# LilyPad-Simblee.net
KiCad netlist of a schematic drawn in EAGLE
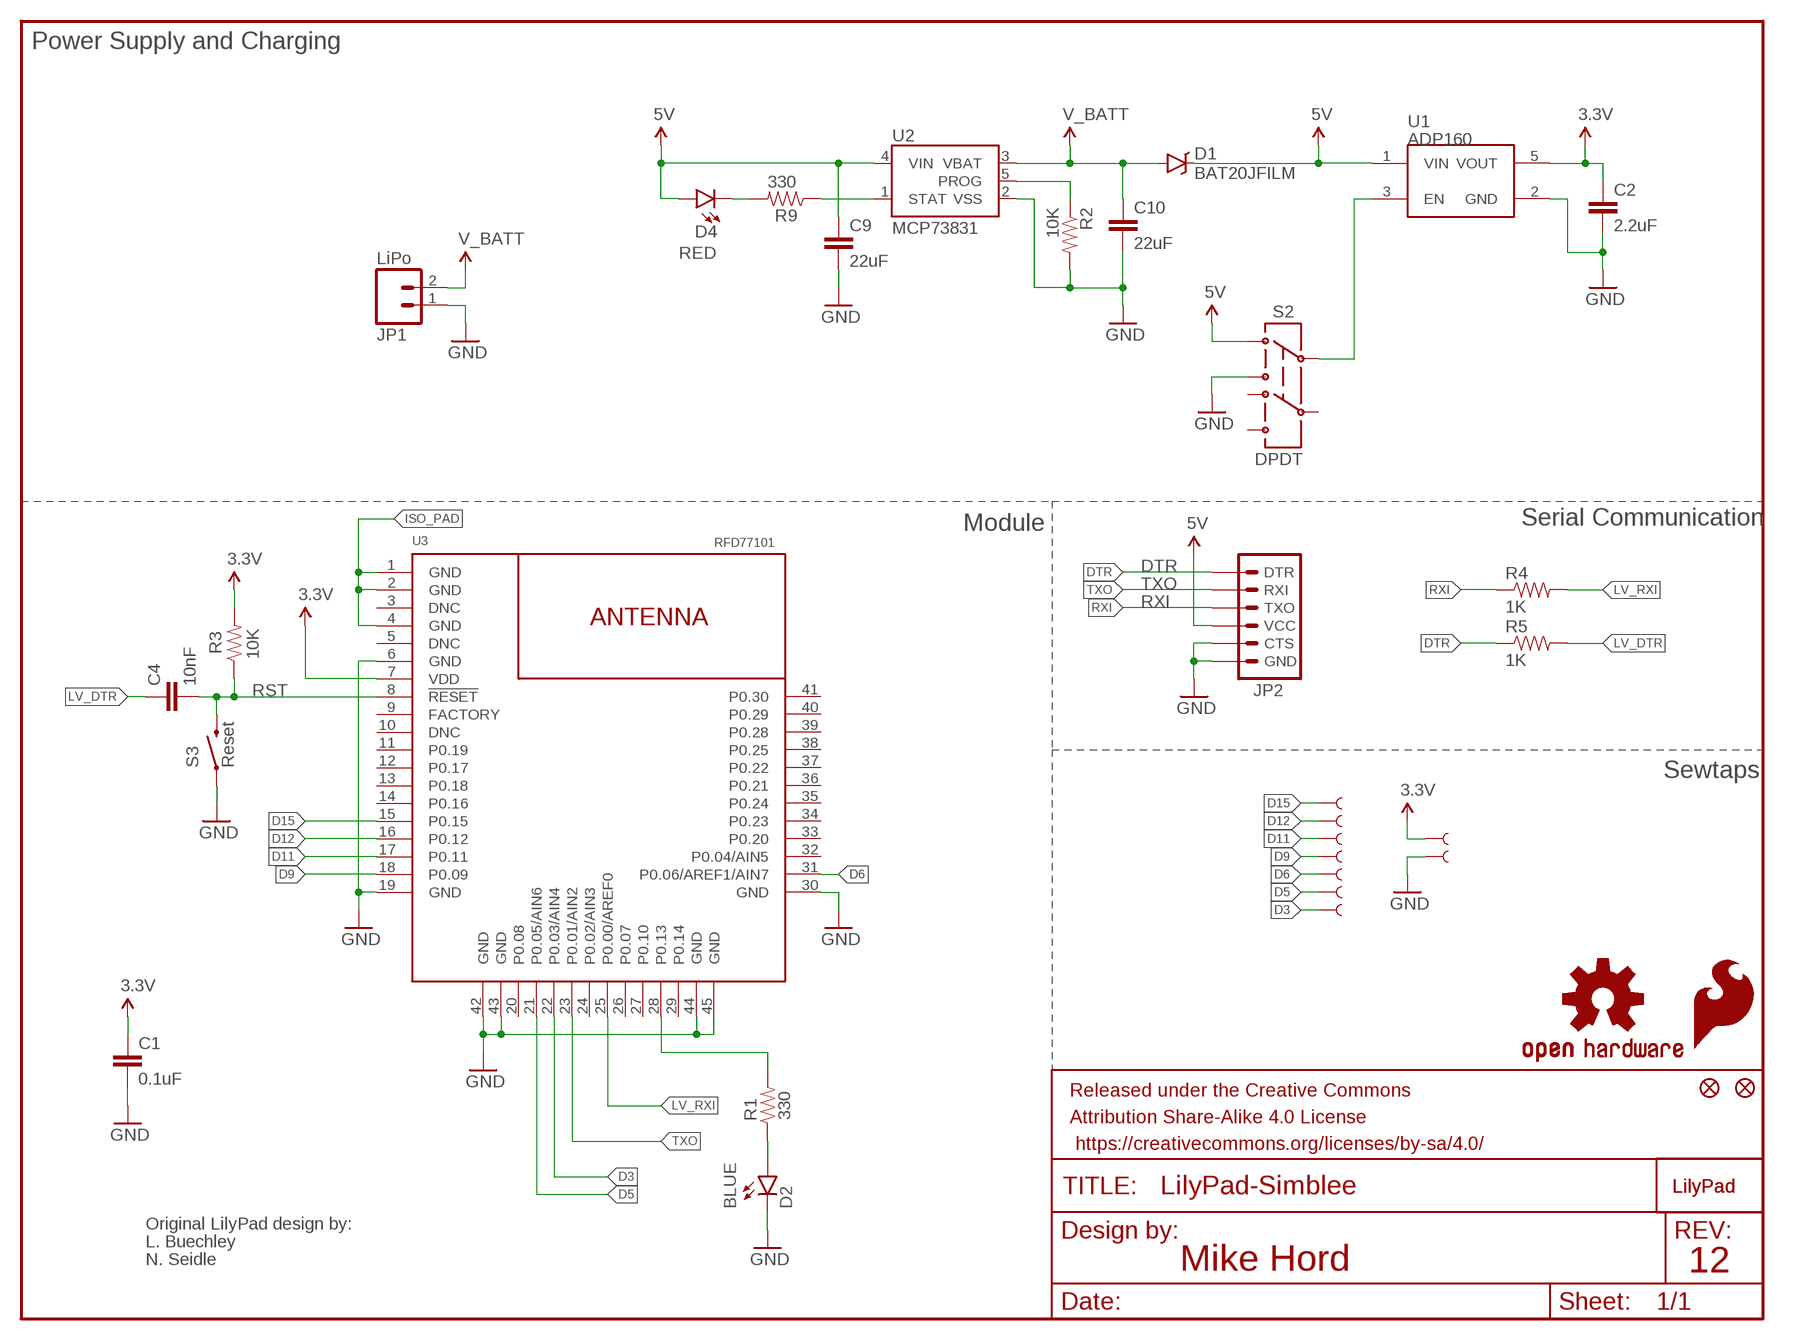
[diagram p0: schematic, sheet 1]

(export (version "E")
  (design (tool "Eeschema 10.0.6"))
  (components
    (comp (ref "A4/18")
      (value "SEWTAP9")
      (footprint "eagle-import:PETAL-LONG-1-2SIDE")
      (libsource (lib "eagle-import") (part "SEWTAP9"))
    )
    (comp (ref "A5/19")
      (value "SEWTAP9")
      (footprint "eagle-import:PETAL-LONG-1-2SIDE")
      (libsource (lib "eagle-import") (part "SEWTAP9"))
    )
    (comp (ref "C1")
      (value "0.1uF")
      (footprint "eagle-import:0603-CAP")
      (libsource (lib "eagle-import") (part "0.1UF-25V(+80/-20%)(0603)"))
    )
    (comp (ref "C2")
      (value "2.2uF")
      (footprint "eagle-import:0603-CAP")
      (libsource (lib "eagle-import") (part "2.2UF-10V-20%(0603)"))
    )
    (comp (ref "C4")
      (value "10nF")
      (footprint "eagle-import:0603-CAP")
      (libsource (lib "eagle-import") (part "10NF/10000PF-50V-10%(0603)"))
    )
    (comp (ref "C9")
      (value "22uF")
      (footprint "eagle-import:0805")
      (libsource (lib "eagle-import") (part "22UF-6.3V-20%(0805)"))
    )
    (comp (ref "C10")
      (value "22uF")
      (footprint "eagle-import:0805")
      (libsource (lib "eagle-import") (part "22UF-6.3V-20%(0805)"))
    )
    (comp (ref "D1")
      (value "BAT20JFILM")
      (footprint "eagle-import:SOD-323")
      (libsource (lib "eagle-import") (part "BAT20JFILM"))
    )
    (comp (ref "D2")
      (value "BLUE")
      (footprint "eagle-import:LED-0603")
      (libsource (lib "eagle-import") (part "LED-BLUE0603"))
    )
    (comp (ref "D4")
      (value "RED")
      (footprint "eagle-import:LED-0603")
      (libsource (lib "eagle-import") (part "LED-RED0603"))
    )
    (comp (ref "FID1")
      (value "FIDUCIALUFIDUCIAL")
      (footprint "eagle-import:MICRO-FIDUCIAL")
      (libsource (lib "eagle-import") (part "FIDUCIALUFIDUCIAL"))
    )
    (comp (ref "FID2")
      (value "FIDUCIALUFIDUCIAL")
      (footprint "eagle-import:MICRO-FIDUCIAL")
      (libsource (lib "eagle-import") (part "FIDUCIALUFIDUCIAL"))
    )
    (comp (ref "FRAME1")
      (value "FRAME-LETTER")
      (footprint "eagle-import:CREATIVE_COMMONS")
      (libsource (lib "eagle-import") (part "FRAME-LETTER"))
    )
    (comp (ref "JP1")
      (value "LiPo")
      (footprint "eagle-import:JST-2-SMD")
      (libsource (lib "eagle-import") (part "M02-JST-2MM-SMT"))
    )
    (comp (ref "JP2")
      (value "ARDUINO_SERIAL_PROGRAMSMD")
      (footprint "eagle-import:1X06-SMD")
      (fields (field (name "PROD_ID") "CONN-08971"))
      (libsource (lib "eagle-import") (part "ARDUINO_SERIAL_PROGRAMSMD"))
    )
    (comp (ref "LOGO1")
      (value "SFE_LOGO_FLAME.1COP")
      (footprint "eagle-import:SFE_LOGO_FLAME_COPPER_.1")
      (libsource (lib "eagle-import") (part "SFE_LOGO_FLAME.1COP"))
    )
    (comp (ref "LOGO2")
      (value "OSHW-LOGOS-COPPER")
      (footprint "eagle-import:OSHW-LOGO-S_COPPER")
      (libsource (lib "eagle-import") (part "OSHW-LOGOS-COPPER"))
    )
    (comp (ref "R1")
      (value "330")
      (footprint "eagle-import:0603-RES")
      (libsource (lib "eagle-import") (part "330OHM1/10W1%(0603)"))
    )
    (comp (ref "R2")
      (value "10K")
      (footprint "eagle-import:0603-RES")
      (libsource (lib "eagle-import") (part "10KOHM-1/10W-1%(0603)0603"))
    )
    (comp (ref "R3")
      (value "10K")
      (footprint "eagle-import:0603-RES")
      (libsource (lib "eagle-import") (part "10KOHM-1/10W-1%(0603)0603"))
    )
    (comp (ref "R4")
      (value "1K")
      (footprint "eagle-import:0603-RES")
      (libsource (lib "eagle-import") (part "1KOHM-1/10W-1%(0603)"))
    )
    (comp (ref "R5")
      (value "1K")
      (footprint "eagle-import:0603-RES")
      (libsource (lib "eagle-import") (part "1KOHM-1/10W-1%(0603)"))
    )
    (comp (ref "R9")
      (value "330")
      (footprint "eagle-import:0603-RES")
      (libsource (lib "eagle-import") (part "330OHM1/10W1%(0603)"))
    )
    (comp (ref "S2")
      (value "DPDT")
      (footprint "eagle-import:AYZ0202")
      (libsource (lib "eagle-import") (part "SWITCH-DPDTAYZ0202"))
    )
    (comp (ref "S3")
      (value "Reset")
      (footprint "eagle-import:TACTILE-SWITCH-SMD")
      (libsource (lib "eagle-import") (part "SWITCH-MOMENTARY-2SMD"))
    )
    (comp (ref "U$1")
      (value "LOGO-LPL")
      (footprint "eagle-import:LOGO-L")
      (libsource (lib "eagle-import") (part "LOGO-LPL"))
    )
    (comp (ref "U$2")
      (value "LOGO-LPLP")
      (footprint "eagle-import:LOGO-LILYPAD")
      (libsource (lib "eagle-import") (part "LOGO-LPLP"))
    )
    (comp (ref "U$4")
      (value "SEWTAP9")
      (footprint "eagle-import:PETAL-LONG-1-2SIDE")
      (libsource (lib "eagle-import") (part "SEWTAP9"))
    )
    (comp (ref "U$35")
      (value "SEWTAP9")
      (footprint "eagle-import:PETAL-LONG-1-2SIDE")
      (libsource (lib "eagle-import") (part "SEWTAP9"))
    )
    (comp (ref "U$37")
      (value "SEWTAP9")
      (footprint "eagle-import:PETAL-LONG-1-2SIDE")
      (libsource (lib "eagle-import") (part "SEWTAP9"))
    )
    (comp (ref "U$39")
      (value "SEWTAP9")
      (footprint "eagle-import:PETAL-LONG-1-2SIDE")
      (libsource (lib "eagle-import") (part "SEWTAP9"))
    )
    (comp (ref "U$41")
      (value "SEWTAP9")
      (footprint "eagle-import:PETAL-LONG-1-2SIDE")
      (libsource (lib "eagle-import") (part "SEWTAP9"))
    )
    (comp (ref "U$43")
      (value "SEWTAP9")
      (footprint "eagle-import:PETAL-LONG-1-2SIDE")
      (libsource (lib "eagle-import") (part "SEWTAP9"))
    )
    (comp (ref "U$45")
      (value "SEWTAP9")
      (footprint "eagle-import:PETAL-LONG-1-2SIDE")
      (libsource (lib "eagle-import") (part "SEWTAP9"))
    )
    (comp (ref "U1")
      (value "ADP160")
      (footprint "eagle-import:SOT23-5")
      (libsource (lib "eagle-import") (part "ADP160"))
    )
    (comp (ref "U2")
      (value "MCP73831")
      (footprint "eagle-import:SOT23-5")
      (libsource (lib "eagle-import") (part "MCP73831"))
    )
    (comp (ref "U3")
      (value "RFD77101")
      (footprint "eagle-import:RFD77101")
      (libsource (lib "eagle-import") (part "RFD77101"))
    )
  )
  (nets
    (net (code "1") (name "/RST") (class "Default")
      (node (ref "C4") (pin "2") (pinfunction "2_2") (pintype "passive"))
      (node (ref "R3") (pin "1") (pinfunction "1_1") (pintype "passive"))
      (node (ref "S3") (pin "3") (pinfunction "2_3") (pintype "passive"))
      (node (ref "U3") (pin "8") (pinfunction "~{RESET}_8") (pintype "input"))
    )
    (net (code "2") (name "3.3V") (class "Default")
      (node (ref "C1") (pin "1") (pinfunction "1_1") (pintype "passive"))
      (node (ref "C2") (pin "1") (pinfunction "1_1") (pintype "passive"))
      (node (ref "R3") (pin "2") (pinfunction "2_2") (pintype "passive"))
      (node (ref "U$43") (pin "1") (pinfunction "1_1") (pintype "bidirectional"))
      (node (ref "U1") (pin "5") (pinfunction "VOUT_5") (pintype "bidirectional"))
      (node (ref "U3") (pin "7") (pinfunction "VDD_7") (pintype "power_in"))
    )
    (net (code "3") (name "5V") (class "Default")
      (node (ref "C9") (pin "1") (pinfunction "1_1") (pintype "passive"))
      (node (ref "D1") (pin "C") (pinfunction "C_C") (pintype "passive"))
      (node (ref "D4") (pin "A") (pinfunction "A_A") (pintype "passive"))
      (node (ref "JP2") (pin "4") (pinfunction "VCC_4") (pintype "passive"))
      (node (ref "S2") (pin "1") (pinfunction "1_1") (pintype "bidirectional"))
      (node (ref "U1") (pin "1") (pinfunction "VIN_1") (pintype "bidirectional"))
      (node (ref "U2") (pin "4") (pinfunction "VIN_4") (pintype "power_in"))
    )
    (net (code "4") (name "D3") (class "Default")
      (node (ref "A5/19") (pin "1") (pinfunction "1_1") (pintype "bidirectional"))
      (node (ref "U3") (pin "22") (pinfunction "P0.03/AIN4_22") (pintype "bidirectional"))
    )
    (net (code "5") (name "D5") (class "Default")
      (node (ref "U$39") (pin "1") (pinfunction "1_1") (pintype "bidirectional"))
      (node (ref "U3") (pin "21") (pinfunction "P0.05/AIN6_21") (pintype "bidirectional"))
    )
    (net (code "6") (name "D6") (class "Default")
      (node (ref "A4/18") (pin "1") (pinfunction "1_1") (pintype "bidirectional"))
      (node (ref "U3") (pin "31") (pinfunction "P0.06/AREF1/AIN7_31") (pintype "bidirectional"))
    )
    (net (code "7") (name "D9") (class "Default")
      (node (ref "U$4") (pin "1") (pinfunction "1_1") (pintype "bidirectional"))
      (node (ref "U3") (pin "18") (pinfunction "P0.09_18") (pintype "bidirectional"))
    )
    (net (code "8") (name "D11") (class "Default")
      (node (ref "U$45") (pin "1") (pinfunction "1_1") (pintype "bidirectional"))
      (node (ref "U3") (pin "17") (pinfunction "P0.11_17") (pintype "bidirectional"))
    )
    (net (code "9") (name "D12") (class "Default")
      (node (ref "U$37") (pin "1") (pinfunction "1_1") (pintype "bidirectional"))
      (node (ref "U3") (pin "16") (pinfunction "P0.12_16") (pintype "bidirectional"))
    )
    (net (code "10") (name "D15") (class "Default")
      (node (ref "U$35") (pin "1") (pinfunction "1_1") (pintype "bidirectional"))
      (node (ref "U3") (pin "15") (pinfunction "P0.15_15") (pintype "bidirectional"))
    )
    (net (code "11") (name "DTR") (class "Default")
      (node (ref "JP2") (pin "1") (pinfunction "DTR_1") (pintype "passive"))
      (node (ref "R5") (pin "1") (pinfunction "1_1") (pintype "passive"))
    )
    (net (code "12") (name "GND") (class "Default")
      (node (ref "C1") (pin "2") (pinfunction "2_2") (pintype "passive"))
      (node (ref "C10") (pin "2") (pinfunction "2_2") (pintype "passive"))
      (node (ref "C2") (pin "2") (pinfunction "2_2") (pintype "passive"))
      (node (ref "C9") (pin "2") (pinfunction "2_2") (pintype "passive"))
      (node (ref "D2") (pin "C") (pinfunction "C_C") (pintype "passive"))
      (node (ref "JP1") (pin "1") (pinfunction "2_1") (pintype "passive"))
      (node (ref "JP2") (pin "5") (pinfunction "CTS_5") (pintype "passive"))
      (node (ref "JP2") (pin "6") (pinfunction "GND_6") (pintype "passive"))
      (node (ref "R2") (pin "2") (pinfunction "2_2") (pintype "passive"))
      (node (ref "S2") (pin "3") (pinfunction "3_3") (pintype "bidirectional"))
      (node (ref "S3") (pin "1") (pinfunction "1_1") (pintype "passive"))
      (node (ref "U$41") (pin "1") (pinfunction "1_1") (pintype "bidirectional"))
      (node (ref "U1") (pin "2") (pinfunction "GND_2") (pintype "bidirectional"))
      (node (ref "U2") (pin "2") (pinfunction "VSS_2") (pintype "power_in"))
      (node (ref "U3") (pin "19") (pinfunction "GND_19") (pintype "power_in"))
      (node (ref "U3") (pin "30") (pinfunction "GND_30") (pintype "power_in"))
      (node (ref "U3") (pin "42") (pinfunction "GND_42") (pintype "power_in"))
      (node (ref "U3") (pin "43") (pinfunction "GND_43") (pintype "power_in"))
      (node (ref "U3") (pin "44") (pinfunction "GND_44") (pintype "power_in"))
      (node (ref "U3") (pin "45") (pinfunction "GND_45") (pintype "power_in"))
      (node (ref "U3") (pin "6") (pinfunction "GND_6") (pintype "power_in"))
    )
    (net (code "13") (name "ISO_PAD") (class "Default")
      (node (ref "U3") (pin "1") (pinfunction "GND_1") (pintype "power_in"))
      (node (ref "U3") (pin "2") (pinfunction "GND_2") (pintype "power_in"))
      (node (ref "U3") (pin "4") (pinfunction "GND_4") (pintype "power_in"))
    )
    (net (code "14") (name "LV_DTR") (class "Default")
      (node (ref "C4") (pin "1") (pinfunction "1_1") (pintype "passive"))
      (node (ref "R5") (pin "2") (pinfunction "2_2") (pintype "passive"))
    )
    (net (code "15") (name "LV_RXI") (class "Default")
      (node (ref "R4") (pin "2") (pinfunction "2_2") (pintype "passive"))
      (node (ref "U3") (pin "25") (pinfunction "P0.00/AREF0_25") (pintype "bidirectional"))
    )
    (net (code "16") (name "Net-(D2-PadA)") (class "Default")
      (node (ref "D2") (pin "A") (pinfunction "A_A") (pintype "passive"))
      (node (ref "R1") (pin "1") (pinfunction "1_1") (pintype "passive"))
    )
    (net (code "17") (name "Net-(D4-PadC)") (class "Default")
      (node (ref "D4") (pin "C") (pinfunction "C_C") (pintype "passive"))
      (node (ref "R9") (pin "2") (pinfunction "2_2") (pintype "passive"))
    )
    (net (code "18") (name "Net-(U1-EN)") (class "Default")
      (node (ref "S2") (pin "2") (pinfunction "2_2") (pintype "bidirectional"))
      (node (ref "U1") (pin "3") (pinfunction "EN_3") (pintype "bidirectional"))
    )
    (net (code "19") (name "Net-(U2-PROG)") (class "Default")
      (node (ref "R2") (pin "1") (pinfunction "1_1") (pintype "passive"))
      (node (ref "U2") (pin "5") (pinfunction "PROG_5") (pintype "input"))
    )
    (net (code "20") (name "Net-(U2-STAT)") (class "Default")
      (node (ref "R9") (pin "1") (pinfunction "1_1") (pintype "passive"))
      (node (ref "U2") (pin "1") (pinfunction "STAT_1") (pintype "output"))
    )
    (net (code "21") (name "Net-(U3-P0.13)") (class "Default")
      (node (ref "R1") (pin "2") (pinfunction "2_2") (pintype "passive"))
      (node (ref "U3") (pin "28") (pinfunction "P0.13_28") (pintype "bidirectional"))
    )
    (net (code "22") (name "RXI") (class "Default")
      (node (ref "JP2") (pin "3") (pinfunction "TXO_3") (pintype "passive"))
      (node (ref "R4") (pin "1") (pinfunction "1_1") (pintype "passive"))
    )
    (net (code "23") (name "TXO") (class "Default")
      (node (ref "JP2") (pin "2") (pinfunction "RXI_2") (pintype "passive"))
      (node (ref "U3") (pin "23") (pinfunction "P0.01/AIN2_23") (pintype "bidirectional"))
    )
    (net (code "24") (name "V_BATT") (class "Default")
      (node (ref "C10") (pin "1") (pinfunction "1_1") (pintype "passive"))
      (node (ref "D1") (pin "A") (pinfunction "A_A") (pintype "passive"))
      (node (ref "JP1") (pin "2") (pinfunction "1_2") (pintype "passive"))
      (node (ref "U2") (pin "3") (pinfunction "VBAT_3") (pintype "power_in"))
    )
    (net (code "25") (name "unconnected-(S2-Pad4)") (class "Default")
      (node (ref "S2") (pin "4") (pinfunction "4_4") (pintype "bidirectional"))
    )
    (net (code "26") (name "unconnected-(S2-Pad5)") (class "Default")
      (node (ref "S2") (pin "5") (pinfunction "5_5") (pintype "bidirectional"))
    )
    (net (code "27") (name "unconnected-(S2-Pad6)") (class "Default")
      (node (ref "S2") (pin "6") (pinfunction "6_6") (pintype "bidirectional"))
    )
    (net (code "28") (name "unconnected-(U3-DNC-Pad3)") (class "Default")
      (node (ref "U3") (pin "3") (pinfunction "DNC_3") (pintype "no_connect"))
    )
    (net (code "29") (name "unconnected-(U3-DNC-Pad5)") (class "Default")
      (node (ref "U3") (pin "5") (pinfunction "DNC_5") (pintype "no_connect"))
    )
    (net (code "30") (name "unconnected-(U3-DNC-Pad10)") (class "Default")
      (node (ref "U3") (pin "10") (pinfunction "DNC_10") (pintype "no_connect"))
    )
    (net (code "31") (name "unconnected-(U3-FACTORY-Pad9)") (class "Default")
      (node (ref "U3") (pin "9") (pinfunction "FACTORY_9") (pintype "no_connect"))
    )
    (net (code "32") (name "unconnected-(U3-P0.02{slash}AIN3-Pad24)") (class "Default")
      (node (ref "U3") (pin "24") (pinfunction "P0.02/AIN3_24") (pintype "bidirectional"))
    )
    (net (code "33") (name "unconnected-(U3-P0.04{slash}AIN5-Pad32)") (class "Default")
      (node (ref "U3") (pin "32") (pinfunction "P0.04/AIN5_32") (pintype "bidirectional"))
    )
    (net (code "34") (name "unconnected-(U3-P0.07-Pad26)") (class "Default")
      (node (ref "U3") (pin "26") (pinfunction "P0.07_26") (pintype "bidirectional"))
    )
    (net (code "35") (name "unconnected-(U3-P0.08-Pad20)") (class "Default")
      (node (ref "U3") (pin "20") (pinfunction "P0.08_20") (pintype "bidirectional"))
    )
    (net (code "36") (name "unconnected-(U3-P0.10-Pad27)") (class "Default")
      (node (ref "U3") (pin "27") (pinfunction "P0.10_27") (pintype "bidirectional"))
    )
    (net (code "37") (name "unconnected-(U3-P0.14-Pad29)") (class "Default")
      (node (ref "U3") (pin "29") (pinfunction "P0.14_29") (pintype "bidirectional"))
    )
    (net (code "38") (name "unconnected-(U3-P0.16-Pad14)") (class "Default")
      (node (ref "U3") (pin "14") (pinfunction "P0.16_14") (pintype "bidirectional"))
    )
    (net (code "39") (name "unconnected-(U3-P0.17-Pad12)") (class "Default")
      (node (ref "U3") (pin "12") (pinfunction "P0.17_12") (pintype "bidirectional"))
    )
    (net (code "40") (name "unconnected-(U3-P0.18-Pad13)") (class "Default")
      (node (ref "U3") (pin "13") (pinfunction "P0.18_13") (pintype "bidirectional"))
    )
    (net (code "41") (name "unconnected-(U3-P0.19-Pad11)") (class "Default")
      (node (ref "U3") (pin "11") (pinfunction "P0.19_11") (pintype "bidirectional"))
    )
    (net (code "42") (name "unconnected-(U3-P0.20-Pad33)") (class "Default")
      (node (ref "U3") (pin "33") (pinfunction "P0.20_33") (pintype "bidirectional"))
    )
    (net (code "43") (name "unconnected-(U3-P0.21-Pad36)") (class "Default")
      (node (ref "U3") (pin "36") (pinfunction "P0.21_36") (pintype "bidirectional"))
    )
    (net (code "44") (name "unconnected-(U3-P0.22-Pad37)") (class "Default")
      (node (ref "U3") (pin "37") (pinfunction "P0.22_37") (pintype "bidirectional"))
    )
    (net (code "45") (name "unconnected-(U3-P0.23-Pad34)") (class "Default")
      (node (ref "U3") (pin "34") (pinfunction "P0.23_34") (pintype "bidirectional"))
    )
    (net (code "46") (name "unconnected-(U3-P0.24-Pad35)") (class "Default")
      (node (ref "U3") (pin "35") (pinfunction "P0.24_35") (pintype "bidirectional"))
    )
    (net (code "47") (name "unconnected-(U3-P0.25-Pad38)") (class "Default")
      (node (ref "U3") (pin "38") (pinfunction "P0.25_38") (pintype "bidirectional"))
    )
    (net (code "48") (name "unconnected-(U3-P0.28-Pad39)") (class "Default")
      (node (ref "U3") (pin "39") (pinfunction "P0.28_39") (pintype "bidirectional"))
    )
    (net (code "49") (name "unconnected-(U3-P0.29-Pad40)") (class "Default")
      (node (ref "U3") (pin "40") (pinfunction "P0.29_40") (pintype "bidirectional"))
    )
    (net (code "50") (name "unconnected-(U3-P0.30-Pad41)") (class "Default")
      (node (ref "U3") (pin "41") (pinfunction "P0.30_41") (pintype "bidirectional"))
    )
  )
)
